# MICROSD_CARD.net
KiCad netlist of a schematic drawn in Altium Designer
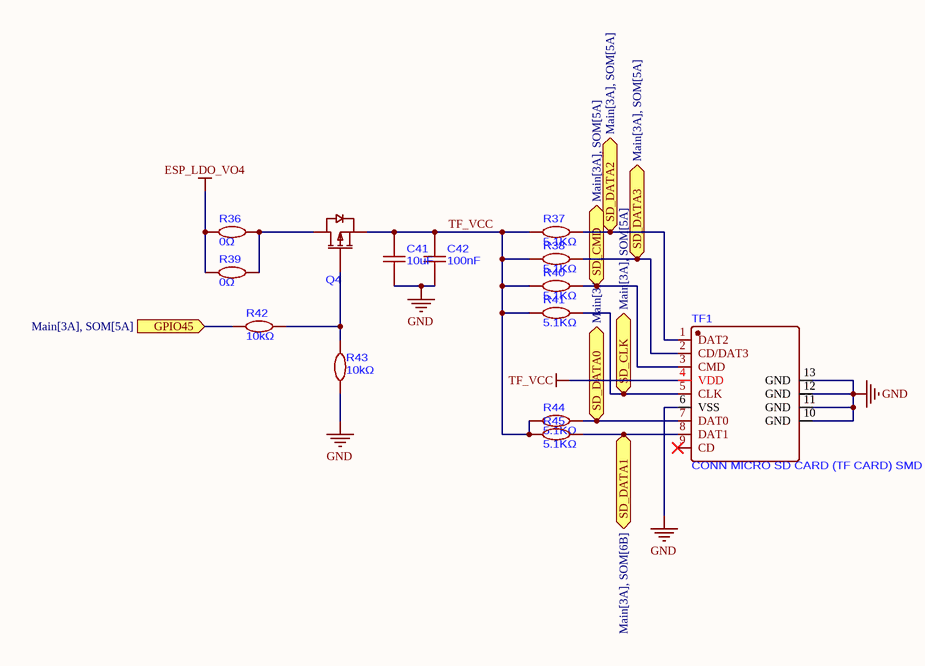
[diagram p0: MICROSD CARD.SchDoc]

(export (version "E")
  (design (tool "Eeschema 10.0.6"))
  (components
    (comp (ref "C41")
      (value "10uF")
      (footprint "C0603")
      (description "25V 10uF X5R ±20% 0603 Ceramic Capacitors ROHS")
      (libsource (lib "Schlib2") (part "CL10A106MA8NRNC"))
    )
    (comp (ref "C42")
      (value "100nF")
      (footprint "C0603")
      (description "50V 100nF X7R ±10% 0603 Ceramic Capacitors ROHS")
      (libsource (lib "Schlib2") (part "CC0603KRX7R9BB104"))
    )
    (comp (ref "Q4")
      (value "MOSFET P-CH 30V 4.3A SOT-23")
      (footprint "SOT-23-3_L2.9-W1.6-P1.90-LS2.8-BR")
      (description "30V 4.3A 48mΩ@10V 2.5V@250uA 1 P-Channel SOT-23 Single FETs, MOSFETs ROHS")
      (libsource (lib "Schlib2") (part "AO3407A"))
    )
    (comp (ref "R36")
      (value "0Ω")
      (footprint "R0603")
      (description "100mW 0Ω 75V Thick Film Resistor ±5% 0603 Chip Resistor - Surface Mount RoHS")
      (libsource (lib "Schlib2") (part "RC0603JR-070RL"))
    )
    (comp (ref "R37")
      (value "5.1KΩ")
      (footprint "R0603")
      (description "100mW 5.1kΩ 75V ±100ppm/℃ Thick Film Resistor ±1% 0603 Chip Resistor - Surface Mount RoHS")
      (libsource (lib "Schlib2") (part "FRC0603F5101TS"))
    )
    (comp (ref "R38")
      (value "5.1KΩ")
      (footprint "R0603")
      (description "100mW 5.1kΩ 75V ±100ppm/℃ Thick Film Resistor ±1% 0603 Chip Resistor - Surface Mount RoHS")
      (libsource (lib "Schlib2") (part "FRC0603F5101TS"))
    )
    (comp (ref "R39")
      (value "0Ω")
      (footprint "R0603")
      (description "100mW 0Ω 75V Thick Film Resistor ±5% 0603 Chip Resistor - Surface Mount RoHS")
      (libsource (lib "Schlib2") (part "RC0603JR-070RL"))
    )
    (comp (ref "R40")
      (value "5.1KΩ")
      (footprint "R0603")
      (description "100mW 5.1kΩ 75V ±100ppm/℃ Thick Film Resistor ±1% 0603 Chip Resistor - Surface Mount RoHS")
      (libsource (lib "Schlib2") (part "FRC0603F5101TS"))
    )
    (comp (ref "R41")
      (value "5.1KΩ")
      (footprint "R0603")
      (description "100mW 5.1kΩ 75V ±100ppm/℃ Thick Film Resistor ±1% 0603 Chip Resistor - Surface Mount RoHS")
      (libsource (lib "Schlib2") (part "FRC0603F5101TS"))
    )
    (comp (ref "R42")
      (value "10kΩ")
      (footprint "R0603")
      (description "100mW 10kΩ 75V ±100ppm/℃ Thick Film Resistor ±1% 0603 Chip Resistor - Surface Mount ROHS")
      (libsource (lib "Schlib2") (part "RC0603FR-0710KL"))
    )
    (comp (ref "R43")
      (value "10kΩ")
      (footprint "R0603")
      (description "100mW 10kΩ 75V ±100ppm/℃ Thick Film Resistor ±1% 0603 Chip Resistor - Surface Mount ROHS")
      (libsource (lib "Schlib2") (part "RC0603FR-0710KL"))
    )
    (comp (ref "R44")
      (value "5.1KΩ")
      (footprint "R0603")
      (description "100mW 5.1kΩ 75V ±100ppm/℃ Thick Film Resistor ±1% 0603 Chip Resistor - Surface Mount RoHS")
      (libsource (lib "Schlib2") (part "FRC0603F5101TS"))
    )
    (comp (ref "R45")
      (value "5.1KΩ")
      (footprint "R0603")
      (description "100mW 5.1kΩ 75V ±100ppm/℃ Thick Film Resistor ±1% 0603 Chip Resistor - Surface Mount RoHS")
      (libsource (lib "Schlib2") (part "FRC0603F5101TS"))
    )
    (comp (ref "TF1")
      (value "CONN MICRO SD CARD (TF CARD) SMD")
      (footprint "TF-SMD_SH_SH-TF-01A")
      (description "-25℃~+85℃ Push-Push 2mm Connector and Ejector MicroSD Card (TF Card) SMD PC Card Sockets RoHS")
      (libsource (lib "Schlib2") (part "SH-TF-01A"))
    )
  )
  (nets
    (net (code "1") (name "/GPIO45") (class "Default")
      (node (ref "R42") (pin "2") (pinfunction "2_2") (pintype "passive"))
    )
    (net (code "2") (name "/SD_CLK") (class "Default")
      (node (ref "R41") (pin "2") (pinfunction "2_2") (pintype "passive"))
      (node (ref "TF1") (pin "5") (pinfunction "CLK_5") (pintype "passive"))
    )
    (net (code "3") (name "/SD_CMD") (class "Default")
      (node (ref "R40") (pin "2") (pinfunction "2_2") (pintype "passive"))
      (node (ref "TF1") (pin "3") (pinfunction "CMD_3") (pintype "passive"))
    )
    (net (code "4") (name "/SD_DATA0") (class "Default")
      (node (ref "R44") (pin "2") (pinfunction "2_2") (pintype "passive"))
      (node (ref "TF1") (pin "7") (pinfunction "DAT0_7") (pintype "passive"))
    )
    (net (code "5") (name "/SD_DATA1") (class "Default")
      (node (ref "R45") (pin "2") (pinfunction "2_2") (pintype "passive"))
      (node (ref "TF1") (pin "8") (pinfunction "DAT1_8") (pintype "passive"))
    )
    (net (code "6") (name "/SD_DATA2") (class "Default")
      (node (ref "R37") (pin "2") (pinfunction "2_2") (pintype "passive"))
      (node (ref "TF1") (pin "1") (pinfunction "DAT2_1") (pintype "passive"))
    )
    (net (code "7") (name "/SD_DATA3") (class "Default")
      (node (ref "R38") (pin "2") (pinfunction "2_2") (pintype "passive"))
      (node (ref "TF1") (pin "2") (pinfunction "CD/DAT3_2") (pintype "passive"))
    )
    (net (code "8") (name "ESP_LDO_VO4") (class "Default")
      (node (ref "R36") (pin "1") (pinfunction "1_1") (pintype "passive"))
      (node (ref "R39") (pin "1") (pinfunction "1_1") (pintype "passive"))
    )
    (net (code "9") (name "GND") (class "Default")
      (node (ref "C41") (pin "1") (pinfunction "1_1") (pintype "passive"))
      (node (ref "C42") (pin "1") (pinfunction "1_1") (pintype "passive"))
      (node (ref "R43") (pin "1") (pinfunction "1_1") (pintype "passive"))
      (node (ref "TF1") (pin "10") (pinfunction "GND_10") (pintype "passive"))
      (node (ref "TF1") (pin "11") (pinfunction "GND_11") (pintype "passive"))
      (node (ref "TF1") (pin "12") (pinfunction "GND_12") (pintype "passive"))
      (node (ref "TF1") (pin "13") (pinfunction "GND_13") (pintype "passive"))
      (node (ref "TF1") (pin "6") (pinfunction "VSS_6") (pintype "passive"))
    )
    (net (code "10") (name "Net-(Q4-D)") (class "Default")
      (node (ref "Q4") (pin "3") (pinfunction "D_3") (pintype "passive"))
      (node (ref "R36") (pin "2") (pinfunction "2_2") (pintype "passive"))
      (node (ref "R39") (pin "2") (pinfunction "2_2") (pintype "passive"))
    )
    (net (code "11") (name "Net-(Q4-G)") (class "Default")
      (node (ref "Q4") (pin "1") (pinfunction "G_1") (pintype "passive"))
      (node (ref "R42") (pin "1") (pinfunction "1_1") (pintype "passive"))
      (node (ref "R43") (pin "2") (pinfunction "2_2") (pintype "passive"))
    )
    (net (code "12") (name "TF_VCC") (class "Default")
      (node (ref "C41") (pin "2") (pinfunction "2_2") (pintype "passive"))
      (node (ref "C42") (pin "2") (pinfunction "2_2") (pintype "passive"))
      (node (ref "Q4") (pin "2") (pinfunction "S_2") (pintype "passive"))
      (node (ref "R37") (pin "1") (pinfunction "1_1") (pintype "passive"))
      (node (ref "R38") (pin "1") (pinfunction "1_1") (pintype "passive"))
      (node (ref "R40") (pin "1") (pinfunction "1_1") (pintype "passive"))
      (node (ref "R41") (pin "1") (pinfunction "1_1") (pintype "passive"))
      (node (ref "R44") (pin "1") (pinfunction "1_1") (pintype "passive"))
      (node (ref "R45") (pin "1") (pinfunction "1_1") (pintype "passive"))
      (node (ref "TF1") (pin "4") (pinfunction "VDD_4") (pintype "passive"))
    )
    (net (code "13") (name "unconnected-(TF1-CD-Pad9)") (class "Default")
      (node (ref "TF1") (pin "9") (pinfunction "CD_9") (pintype "passive+no_connect"))
    )
  )
)
